# power.net
KiCad netlist of a schematic drawn in EAGLE
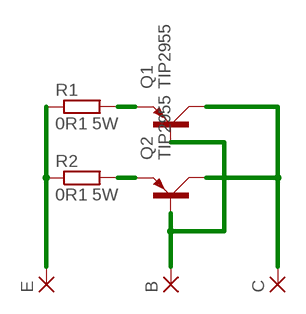
[diagram p0: schematic, sheet 1]

(export (version "E")
  (design (tool "Eeschema 10.0.6"))
  (components
    (comp (ref "B")
      (value "3,81/1,4")
      (footprint "eagle-import:3,81_1,4")
      (libsource (lib "eagle-import") (part "3,81/1,4"))
    )
    (comp (ref "C")
      (value "3,81/1,4")
      (footprint "eagle-import:3,81_1,4")
      (libsource (lib "eagle-import") (part "3,81/1,4"))
    )
    (comp (ref "E")
      (value "3,81/1,4")
      (footprint "eagle-import:3,81_1,4")
      (libsource (lib "eagle-import") (part "3,81/1,4"))
    )
    (comp (ref "Q1")
      (value "TIP2955")
      (footprint "eagle-import:TOP3AV")
      (libsource (lib "eagle-import") (part "TIP2955"))
    )
    (comp (ref "Q2")
      (value "TIP2955")
      (footprint "eagle-import:TOP3AV")
      (libsource (lib "eagle-import") (part "TIP2955"))
    )
    (comp (ref "R1")
      (value "0R1 5W")
      (footprint "eagle-import:0207_15")
      (libsource (lib "eagle-import") (part "R-EU_0207/15"))
    )
    (comp (ref "R2")
      (value "0R1 5W")
      (footprint "eagle-import:0207_15")
      (libsource (lib "eagle-import") (part "R-EU_0207/15"))
    )
  )
  (nets
    (net (code "1") (name "Net-(B-P)") (class "Default")
      (node (ref "B") (pin "1") (pinfunction "P_1") (pintype "passive"))
      (node (ref "Q1") (pin "B") (pinfunction "B_B") (pintype "passive"))
      (node (ref "Q2") (pin "B") (pinfunction "B_B") (pintype "passive"))
    )
    (net (code "2") (name "Net-(C-P)") (class "Default")
      (node (ref "C") (pin "1") (pinfunction "P_1") (pintype "passive"))
      (node (ref "Q1") (pin "C") (pinfunction "C_C") (pintype "passive"))
      (node (ref "Q2") (pin "C") (pinfunction "C_C") (pintype "passive"))
    )
    (net (code "3") (name "Net-(E-P)") (class "Default")
      (node (ref "E") (pin "1") (pinfunction "P_1") (pintype "passive"))
      (node (ref "R1") (pin "1") (pinfunction "1_1") (pintype "passive"))
      (node (ref "R2") (pin "1") (pinfunction "1_1") (pintype "passive"))
    )
    (net (code "4") (name "Net-(Q1-PadE)") (class "Default")
      (node (ref "Q1") (pin "E") (pinfunction "E_E") (pintype "passive"))
      (node (ref "R1") (pin "2") (pinfunction "2_2") (pintype "passive"))
    )
    (net (code "5") (name "Net-(Q2-PadE)") (class "Default")
      (node (ref "Q2") (pin "E") (pinfunction "E_E") (pintype "passive"))
      (node (ref "R2") (pin "2") (pinfunction "2_2") (pintype "passive"))
    )
  )
)
